# Channel_supply.net
KiCad netlist of a schematic drawn in Altium Designer
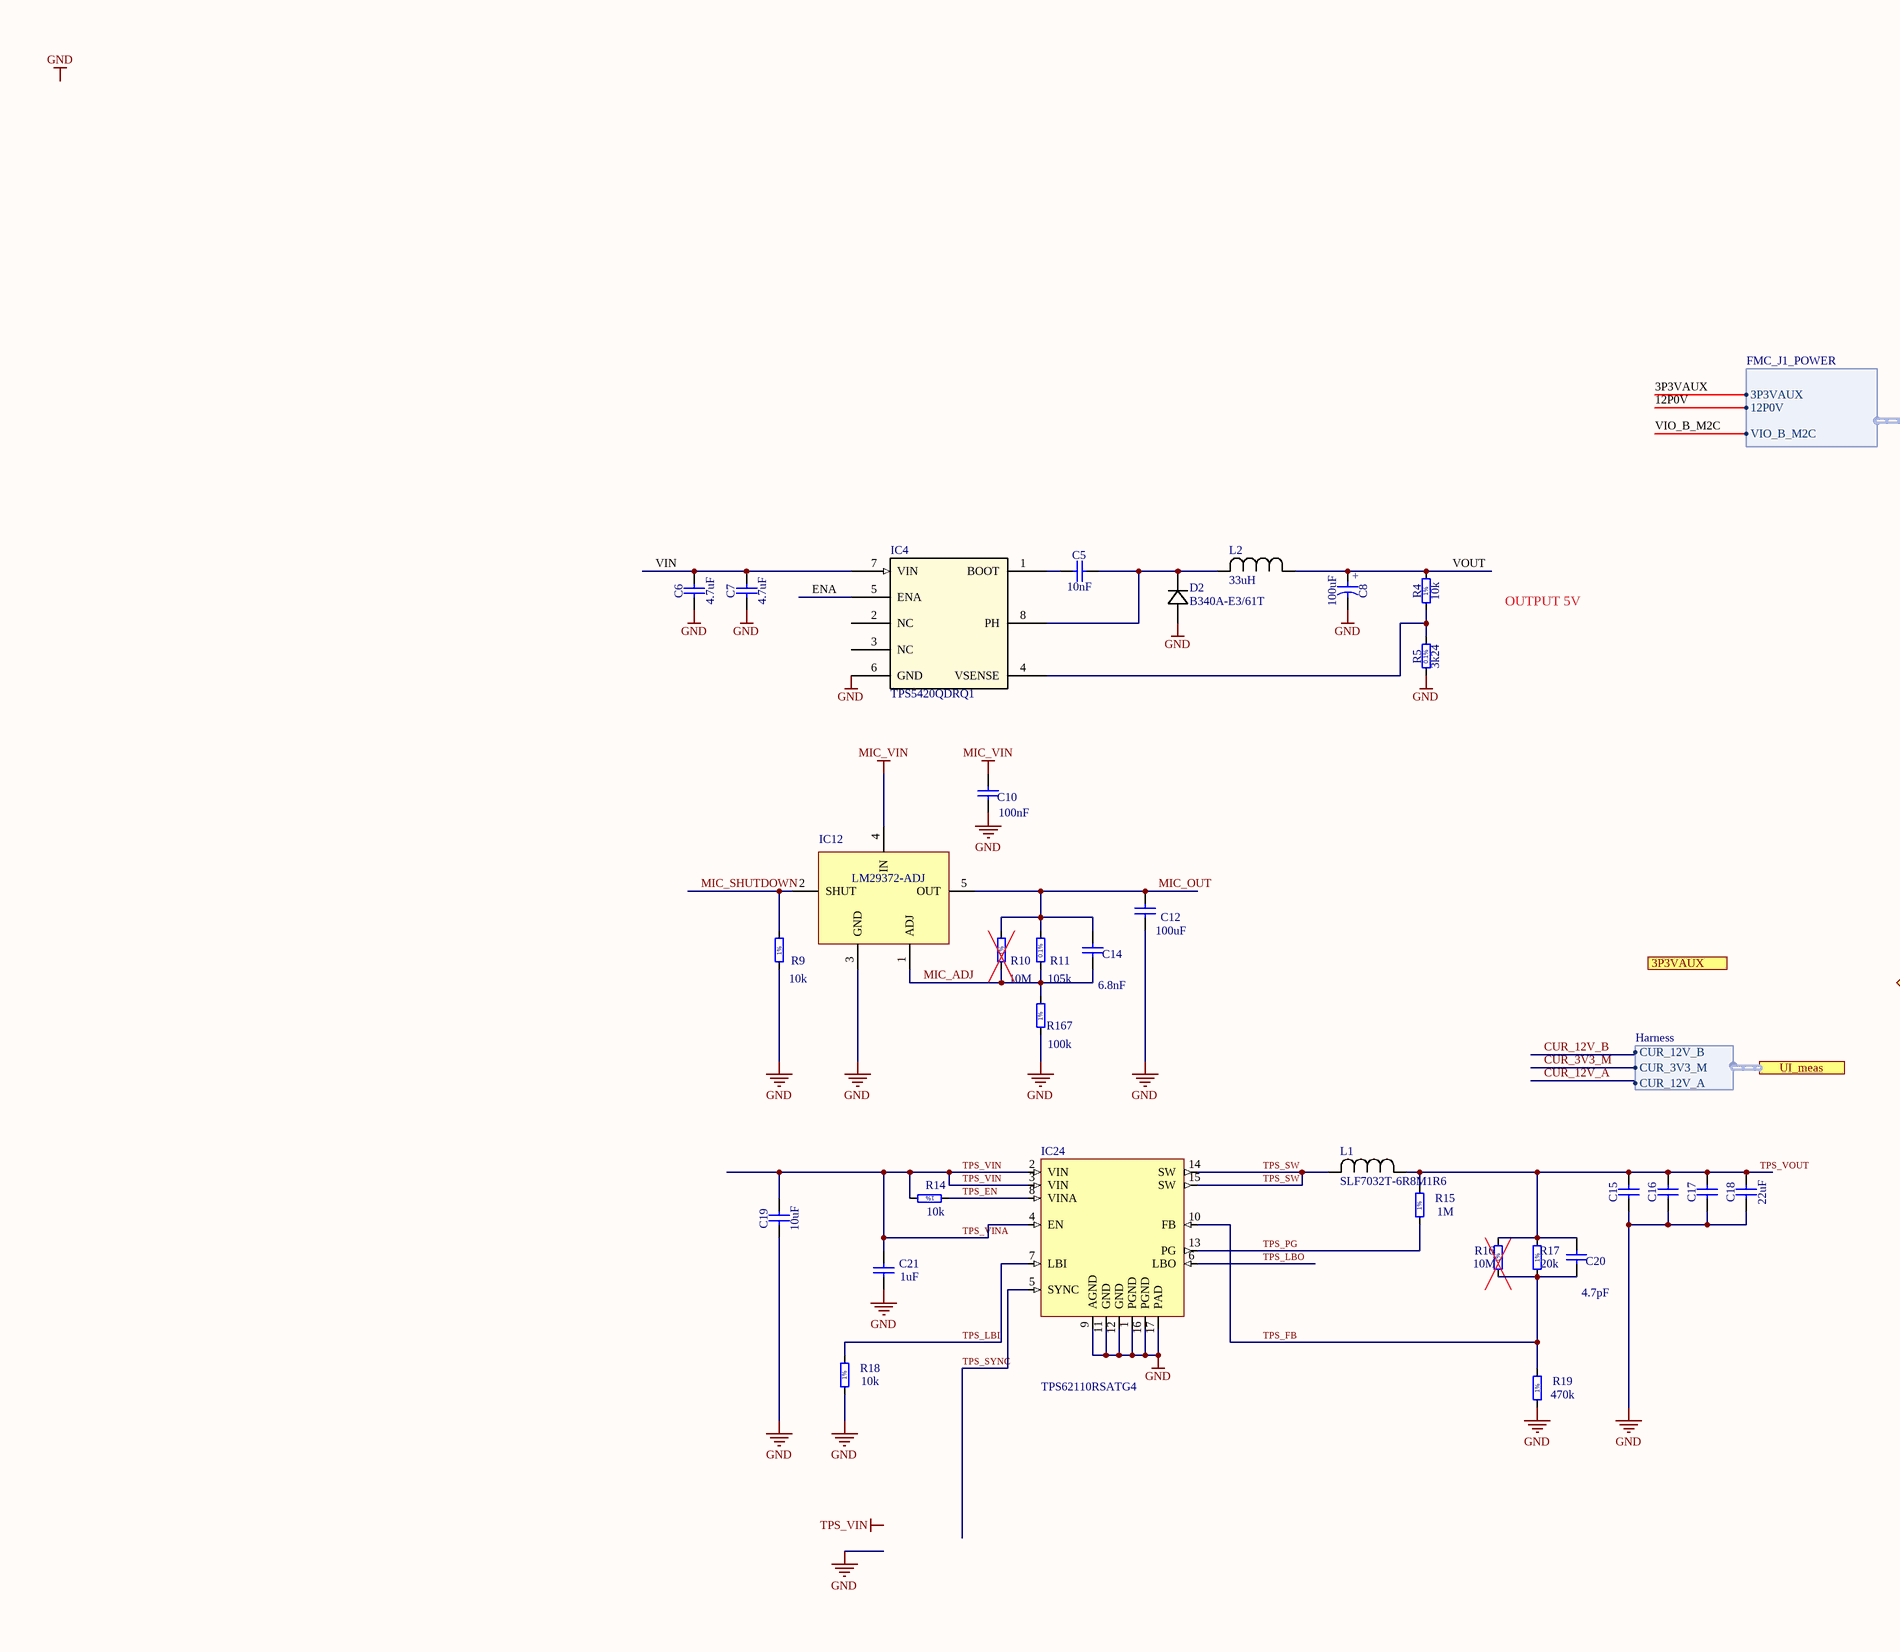
[diagram p0: Channel_supply.SchDoc, left]
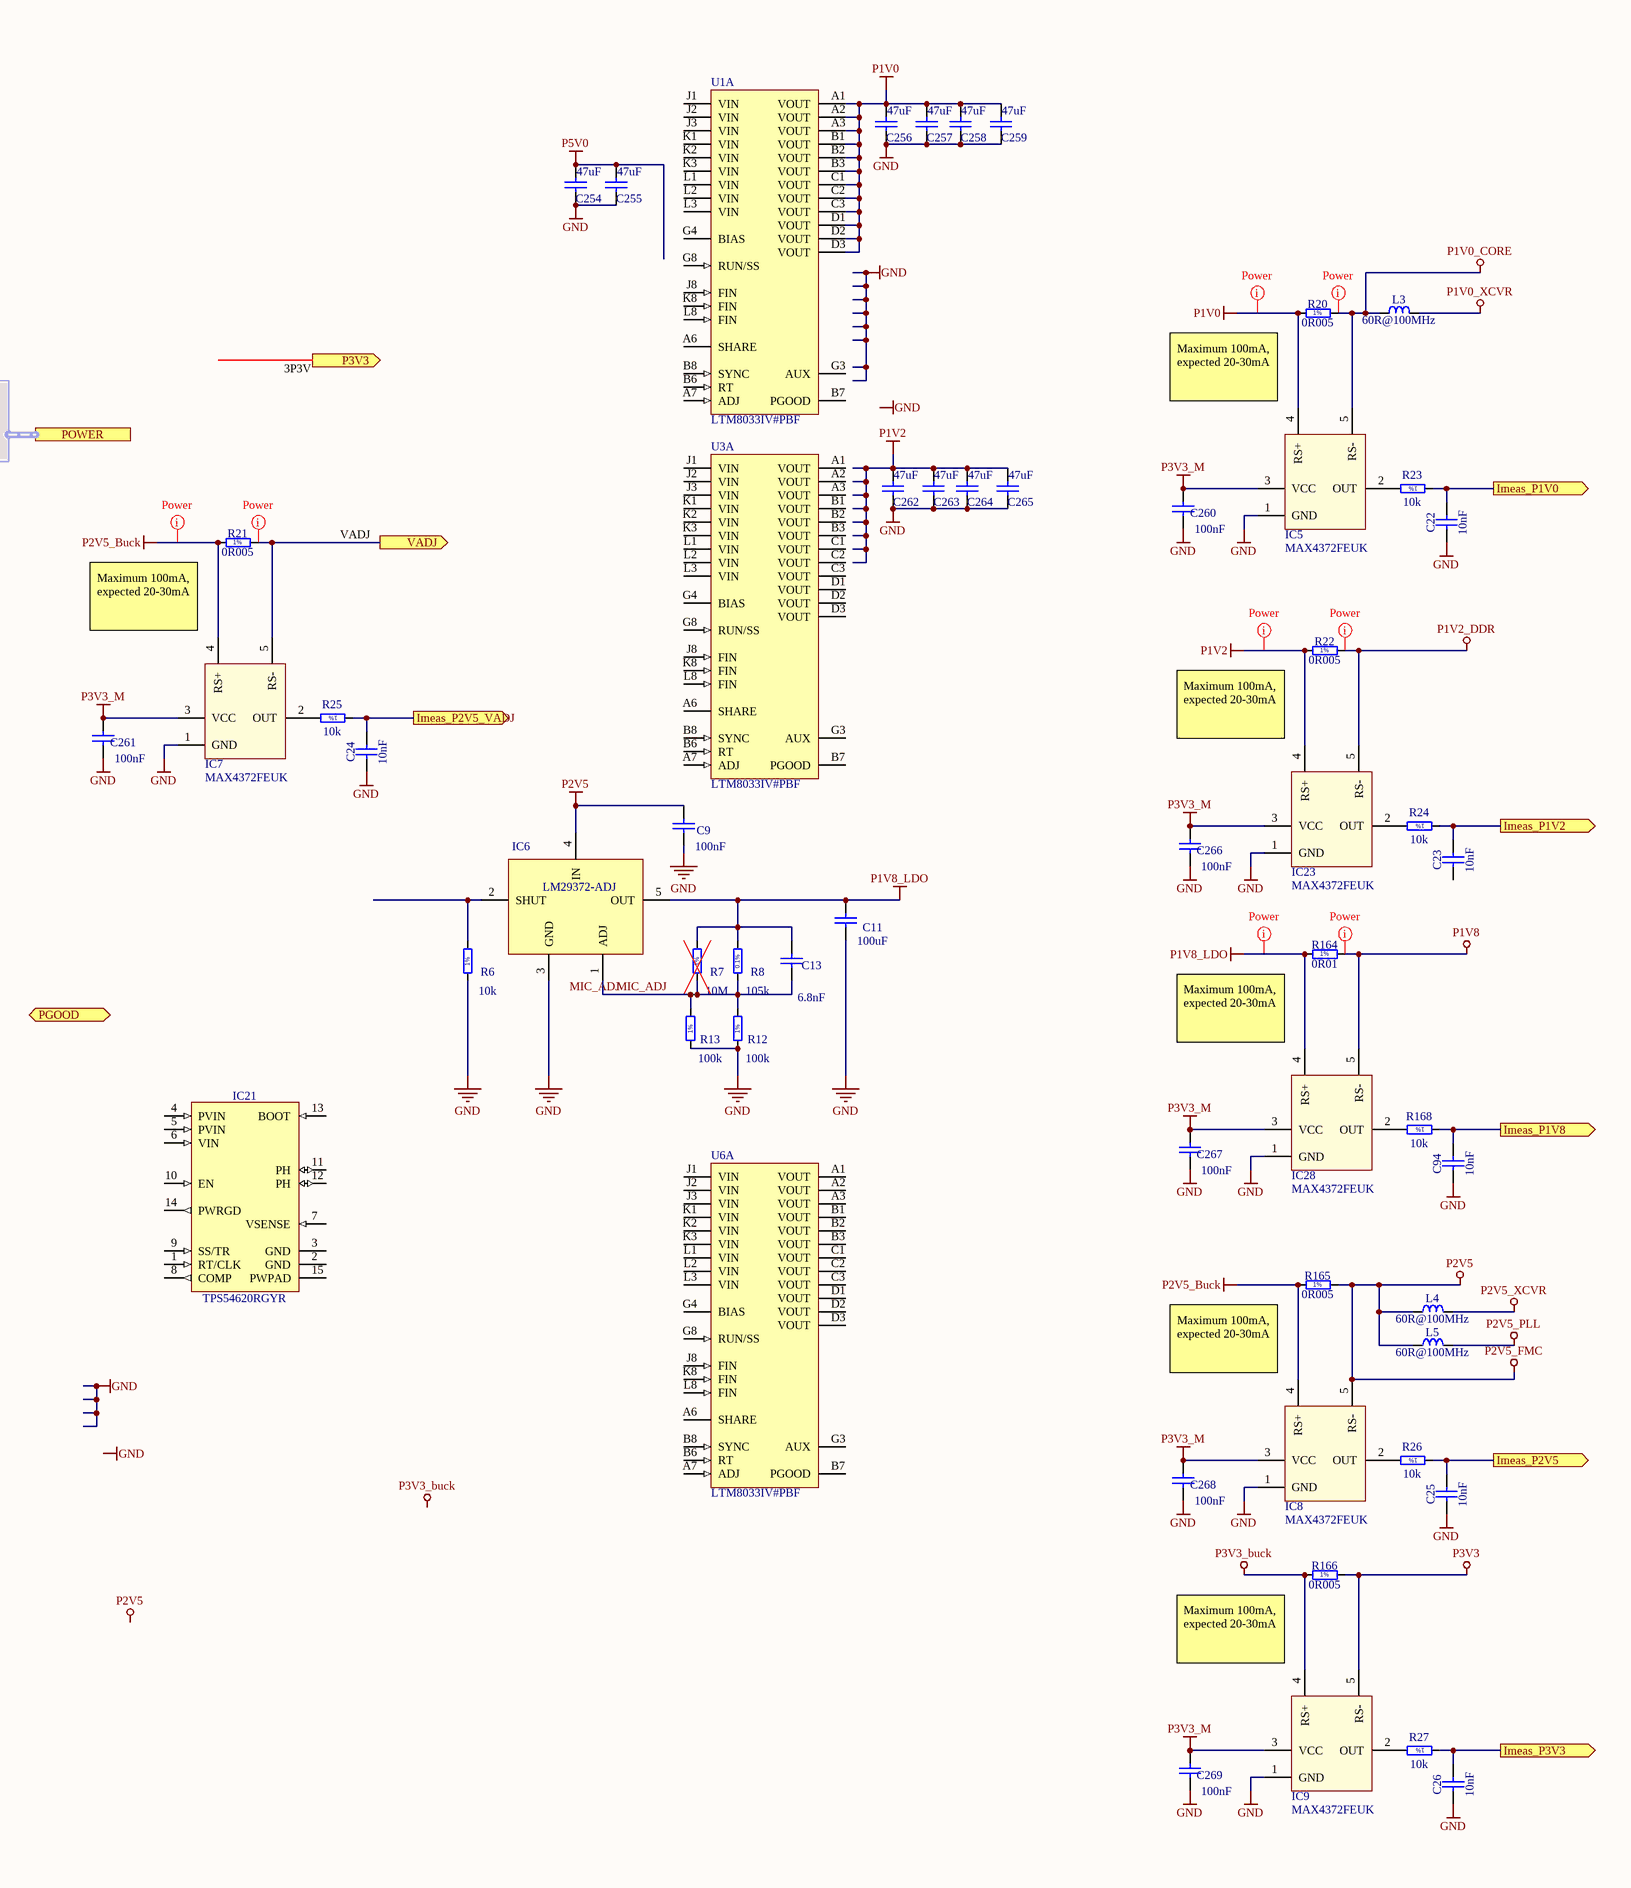
[diagram p1: Channel_supply.SchDoc, right]

(export (version "E")
  (design (tool "Eeschema 10.0.6"))
  (components
    (comp (ref "C5")
      (value "10nF")
      (footprint "CAPC1608X87N")
      (description "Non-polarised capacitor")
      (fields
        (field (name "PART NUMBER") "CC0603_10NF_50V_10%_X7R")
        (field (name "VOLTAGE") "50V")
        (field (name "AUTHOR") "CERN DEM JLC")
      )
      (libsource (lib "Capacitors") (part "Capacitor - non polarized"))
    )
    (comp (ref "C6")
      (value "4.7uF")
      (footprint "CAPC3225X270N")
      (description "Non-polarised capacitor")
      (fields
        (field (name "PART NUMBER") "CC1210_4.7UF_50V_10%_X7R")
        (field (name "VOLTAGE") "50V")
        (field (name "AUTHOR") "CERN DEM JLC")
      )
      (libsource (lib "Capacitors") (part "Capacitor - non polarized"))
    )
    (comp (ref "C7")
      (value "4.7uF")
      (footprint "CAPC3225X270N")
      (description "Non-polarised capacitor")
      (fields
        (field (name "PART NUMBER") "CC1210_4.7UF_50V_10%_X7R")
        (field (name "VOLTAGE") "50V")
        (field (name "AUTHOR") "CERN DEM JLC")
      )
      (libsource (lib "Capacitors") (part "Capacitor - non polarized"))
    )
    (comp (ref "C8")
      (value "100uF")
      (footprint "CAPMP7343X310N")
      (description "Polarised capacitor")
      (fields
        (field (name "PART NUMBER") "100uF 2917 20% ESR=80mOhms AEC-Q200")
        (field (name "VOLTAGE") "10V")
        (field (name "AUTHOR") "CERN DEM JLC")
      )
      (libsource (lib "Capacitors") (part "Capacitor - polarized"))
    )
    (comp (ref "C9")
      (value "100nF")
      (footprint "CAPC1608X87N")
      (description "Non-polarised capacitor")
      (fields
        (field (name "PART NUMBER") "CC0603_100NF_50V_10%_X7R")
        (field (name "VOLTAGE") "50V")
        (field (name "AUTHOR") "CERN DEM JLC")
      )
      (libsource (lib "Capacitors") (part "Capacitor - non polarized"))
    )
    (comp (ref "C10")
      (value "100nF")
      (footprint "CAPC1608X87N")
      (description "Non-polarised capacitor")
      (fields
        (field (name "PART NUMBER") "CC0603_100NF_50V_10%_X7R")
        (field (name "VOLTAGE") "50V")
        (field (name "AUTHOR") "CERN DEM JLC")
      )
      (libsource (lib "Capacitors") (part "Capacitor - non polarized"))
    )
    (comp (ref "C11")
      (value "100uF")
      (footprint "CAPC3216X190N")
      (description "Non-polarised capacitor")
      (fields
        (field (name "PART NUMBER") "CC1206_100UF_10V_20%_X5R")
        (field (name "VOLTAGE") "10V")
        (field (name "AUTHOR") "CERN DEM MR")
      )
      (libsource (lib "Capacitors") (part "Capacitor - non polarized"))
    )
    (comp (ref "C12")
      (value "100uF")
      (footprint "CAPC3216X190N")
      (description "Non-polarised capacitor")
      (fields
        (field (name "PART NUMBER") "CC1206_100UF_10V_20%_X5R")
        (field (name "VOLTAGE") "10V")
        (field (name "AUTHOR") "CERN DEM MR")
      )
      (libsource (lib "Capacitors") (part "Capacitor - non polarized"))
    )
    (comp (ref "C13")
      (value "6.8nF")
      (footprint "CAPC1608X87N")
      (description "Non-polarised capacitor")
      (fields
        (field (name "PART NUMBER") "CC0603_6.8NF_50V_5%_X7R")
        (field (name "VOLTAGE") "50V")
        (field (name "AUTHOR") "CERN DEM JLC")
      )
      (libsource (lib "Capacitors") (part "Capacitor - non polarized"))
    )
    (comp (ref "C14")
      (value "6.8nF")
      (footprint "CAPC1608X87N")
      (description "Non-polarised capacitor")
      (fields
        (field (name "PART NUMBER") "CC0603_6.8NF_50V_5%_X7R")
        (field (name "VOLTAGE") "50V")
        (field (name "AUTHOR") "CERN DEM JLC")
      )
      (libsource (lib "Capacitors") (part "Capacitor - non polarized"))
    )
    (comp (ref "C15")
      (value "22uF")
      (footprint "CAPC3225X270N")
      (description "Non-polarised capacitor")
      (fields
        (field (name "PART NUMBER") "CC1210_22UF_16V_10%_X7R_YUDEN_EMK325B7226KMH")
        (field (name "VOLTAGE") "16V")
        (field (name "AUTHOR") "CERN DEM BC")
      )
      (libsource (lib "Capacitors") (part "Capacitor - non polarized"))
    )
    (comp (ref "C16")
      (value "22uF")
      (footprint "CAPC3225X270N")
      (description "Non-polarised capacitor")
      (fields
        (field (name "PART NUMBER") "CC1210_22UF_16V_10%_X7R_YUDEN_EMK325B7226KMH")
        (field (name "VOLTAGE") "16V")
        (field (name "AUTHOR") "CERN DEM BC")
      )
      (libsource (lib "Capacitors") (part "Capacitor - non polarized"))
    )
    (comp (ref "C17")
      (value "22uF")
      (footprint "CAPC3225X270N")
      (description "Non-polarised capacitor")
      (fields
        (field (name "PART NUMBER") "CC1210_22UF_16V_10%_X7R_YUDEN_EMK325B7226KMH")
        (field (name "VOLTAGE") "16V")
        (field (name "AUTHOR") "CERN DEM BC")
      )
      (libsource (lib "Capacitors") (part "Capacitor - non polarized"))
    )
    (comp (ref "C18")
      (value "22uF")
      (footprint "CAPC3225X270N")
      (description "Non-polarised capacitor")
      (fields
        (field (name "PART NUMBER") "CC1210_22UF_16V_10%_X7R_YUDEN_EMK325B7226KMH")
        (field (name "VOLTAGE") "16V")
        (field (name "AUTHOR") "CERN DEM BC")
      )
      (libsource (lib "Capacitors") (part "Capacitor - non polarized"))
    )
    (comp (ref "C19")
      (value "10uF")
      (footprint "CAPC3225X270N")
      (description "Non-polarised capacitor")
      (fields
        (field (name "PART NUMBER") "CC1210_10UF_25V_10%_X7R")
        (field (name "VOLTAGE") "25V")
        (field (name "AUTHOR") "CERN DEM JLC")
      )
      (libsource (lib "Capacitors") (part "Capacitor - non polarized"))
    )
    (comp (ref "C20")
      (value "4.7pF")
      (footprint "CAPC1608X87N")
      (description "Non-polarised capacitor")
      (fields
        (field (name "PART NUMBER") "CC0603_4.7PF_50V_0.25PF_NP0")
        (field (name "VOLTAGE") "50V")
        (field (name "AUTHOR") "CERN DEM JLC")
      )
      (libsource (lib "Capacitors") (part "Capacitor - non polarized"))
    )
    (comp (ref "C21")
      (value "1uF")
      (footprint "CAPC1608X87N")
      (description "Non-polarised capacitor")
      (fields
        (field (name "PART NUMBER") "CC0603_1UF_25V_10%_X7R")
        (field (name "VOLTAGE") "25V")
        (field (name "AUTHOR") "CERN DEM JLC")
      )
      (libsource (lib "Capacitors") (part "Capacitor - non polarized"))
    )
    (comp (ref "C22")
      (value "10nF")
      (footprint "CAPC1608X87N")
      (description "Non-polarised capacitor")
      (fields
        (field (name "PART NUMBER") "CC0603_10NF_50V_10%_X7R")
        (field (name "VOLTAGE") "50V")
        (field (name "AUTHOR") "CERN DEM JLC")
      )
      (libsource (lib "Capacitors") (part "Capacitor - non polarized"))
    )
    (comp (ref "C23")
      (value "10nF")
      (footprint "CAPC1608X87N")
      (description "Non-polarised capacitor")
      (fields
        (field (name "PART NUMBER") "CC0603_10NF_50V_10%_X7R")
        (field (name "VOLTAGE") "50V")
        (field (name "AUTHOR") "CERN DEM JLC")
      )
      (libsource (lib "Capacitors") (part "Capacitor - non polarized"))
    )
    (comp (ref "C24")
      (value "10nF")
      (footprint "CAPC1608X87N")
      (description "Non-polarised capacitor")
      (fields
        (field (name "PART NUMBER") "CC0603_10NF_50V_10%_X7R")
        (field (name "VOLTAGE") "50V")
        (field (name "AUTHOR") "CERN DEM JLC")
      )
      (libsource (lib "Capacitors") (part "Capacitor - non polarized"))
    )
    (comp (ref "C25")
      (value "10nF")
      (footprint "CAPC1608X87N")
      (description "Non-polarised capacitor")
      (fields
        (field (name "PART NUMBER") "CC0603_10NF_50V_10%_X7R")
        (field (name "VOLTAGE") "50V")
        (field (name "AUTHOR") "CERN DEM JLC")
      )
      (libsource (lib "Capacitors") (part "Capacitor - non polarized"))
    )
    (comp (ref "C26")
      (value "10nF")
      (footprint "CAPC1608X87N")
      (description "Non-polarised capacitor")
      (fields
        (field (name "PART NUMBER") "CC0603_10NF_50V_10%_X7R")
        (field (name "VOLTAGE") "50V")
        (field (name "AUTHOR") "CERN DEM JLC")
      )
      (libsource (lib "Capacitors") (part "Capacitor - non polarized"))
    )
    (comp (ref "C94")
      (value "10nF")
      (footprint "CAPC1608X87N")
      (description "Non-polarised capacitor")
      (fields
        (field (name "PART NUMBER") "CC0603_10NF_50V_10%_X7R")
        (field (name "VOLTAGE") "50V")
        (field (name "AUTHOR") "CERN DEM JLC")
      )
      (libsource (lib "Capacitors") (part "Capacitor - non polarized"))
    )
    (comp (ref "C254")
      (value "47uF")
      (footprint "CAPC2012X140N")
      (description "Non-polarised capacitor")
      (fields
        (field (name "PART NUMBER") "CC0805_47UF_6.3V_20%_X5R")
        (field (name "MANUFACTURER") "GENERIC")
        (field (name "AUTHOR") "CERN DEM JLC")
      )
      (libsource (lib "Capacitors") (part "Capacitor - non polarized"))
    )
    (comp (ref "C255")
      (value "47uF")
      (footprint "CAPC2012X140N")
      (description "Non-polarised capacitor")
      (fields
        (field (name "PART NUMBER") "CC0805_47UF_6.3V_20%_X5R")
        (field (name "MANUFACTURER") "GENERIC")
        (field (name "AUTHOR") "CERN DEM JLC")
      )
      (libsource (lib "Capacitors") (part "Capacitor - non polarized"))
    )
    (comp (ref "C256")
      (value "47uF")
      (footprint "CAPC2012X140N")
      (description "Non-polarised capacitor")
      (fields
        (field (name "PART NUMBER") "CC0805_47UF_6.3V_20%_X5R")
        (field (name "MANUFACTURER") "GENERIC")
        (field (name "AUTHOR") "CERN DEM JLC")
      )
      (libsource (lib "Capacitors") (part "Capacitor - non polarized"))
    )
    (comp (ref "C257")
      (value "47uF")
      (footprint "CAPC2012X140N")
      (description "Non-polarised capacitor")
      (fields
        (field (name "PART NUMBER") "CC0805_47UF_6.3V_20%_X5R")
        (field (name "MANUFACTURER") "GENERIC")
        (field (name "AUTHOR") "CERN DEM JLC")
      )
      (libsource (lib "Capacitors") (part "Capacitor - non polarized"))
    )
    (comp (ref "C258")
      (value "47uF")
      (footprint "CAPC2012X140N")
      (description "Non-polarised capacitor")
      (fields
        (field (name "PART NUMBER") "CC0805_47UF_6.3V_20%_X5R")
        (field (name "MANUFACTURER") "GENERIC")
        (field (name "AUTHOR") "CERN DEM JLC")
      )
      (libsource (lib "Capacitors") (part "Capacitor - non polarized"))
    )
    (comp (ref "C259")
      (value "47uF")
      (footprint "CAPC2012X140N")
      (description "Non-polarised capacitor")
      (fields
        (field (name "PART NUMBER") "CC0805_47UF_6.3V_20%_X5R")
        (field (name "MANUFACTURER") "GENERIC")
        (field (name "AUTHOR") "CERN DEM JLC")
      )
      (libsource (lib "Capacitors") (part "Capacitor - non polarized"))
    )
    (comp (ref "C260")
      (value "100nF")
      (footprint "CAPC1608X87N")
      (description "Non-polarised capacitor")
      (fields
        (field (name "PART NUMBER") "CC0603_100NF_50V_10%_X7R")
        (field (name "VOLTAGE") "50V")
        (field (name "AUTHOR") "CERN DEM JLC")
      )
      (libsource (lib "Capacitors") (part "Capacitor - non polarized"))
    )
    (comp (ref "C261")
      (value "100nF")
      (footprint "CAPC1608X87N")
      (description "Non-polarised capacitor")
      (fields
        (field (name "PART NUMBER") "CC0603_100NF_50V_10%_X7R")
        (field (name "VOLTAGE") "50V")
        (field (name "AUTHOR") "CERN DEM JLC")
      )
      (libsource (lib "Capacitors") (part "Capacitor - non polarized"))
    )
    (comp (ref "C262")
      (value "47uF")
      (footprint "CAPC2012X140N")
      (description "Non-polarised capacitor")
      (fields
        (field (name "PART NUMBER") "CC0805_47UF_6.3V_20%_X5R")
        (field (name "MANUFACTURER") "GENERIC")
        (field (name "AUTHOR") "CERN DEM JLC")
      )
      (libsource (lib "Capacitors") (part "Capacitor - non polarized"))
    )
    (comp (ref "C263")
      (value "47uF")
      (footprint "CAPC2012X140N")
      (description "Non-polarised capacitor")
      (fields
        (field (name "PART NUMBER") "CC0805_47UF_6.3V_20%_X5R")
        (field (name "MANUFACTURER") "GENERIC")
        (field (name "AUTHOR") "CERN DEM JLC")
      )
      (libsource (lib "Capacitors") (part "Capacitor - non polarized"))
    )
    (comp (ref "C264")
      (value "47uF")
      (footprint "CAPC2012X140N")
      (description "Non-polarised capacitor")
      (fields
        (field (name "PART NUMBER") "CC0805_47UF_6.3V_20%_X5R")
        (field (name "MANUFACTURER") "GENERIC")
        (field (name "AUTHOR") "CERN DEM JLC")
      )
      (libsource (lib "Capacitors") (part "Capacitor - non polarized"))
    )
    (comp (ref "C265")
      (value "47uF")
      (footprint "CAPC2012X140N")
      (description "Non-polarised capacitor")
      (fields
        (field (name "PART NUMBER") "CC0805_47UF_6.3V_20%_X5R")
        (field (name "MANUFACTURER") "GENERIC")
        (field (name "AUTHOR") "CERN DEM JLC")
      )
      (libsource (lib "Capacitors") (part "Capacitor - non polarized"))
    )
    (comp (ref "C266")
      (value "100nF")
      (footprint "CAPC1608X87N")
      (description "Non-polarised capacitor")
      (fields
        (field (name "PART NUMBER") "CC0603_100NF_50V_10%_X7R")
        (field (name "VOLTAGE") "50V")
        (field (name "AUTHOR") "CERN DEM JLC")
      )
      (libsource (lib "Capacitors") (part "Capacitor - non polarized"))
    )
    (comp (ref "C267")
      (value "100nF")
      (footprint "CAPC1608X87N")
      (description "Non-polarised capacitor")
      (fields
        (field (name "PART NUMBER") "CC0603_100NF_50V_10%_X7R")
        (field (name "VOLTAGE") "50V")
        (field (name "AUTHOR") "CERN DEM JLC")
      )
      (libsource (lib "Capacitors") (part "Capacitor - non polarized"))
    )
    (comp (ref "C268")
      (value "100nF")
      (footprint "CAPC1608X87N")
      (description "Non-polarised capacitor")
      (fields
        (field (name "PART NUMBER") "CC0603_100NF_50V_10%_X7R")
        (field (name "VOLTAGE") "50V")
        (field (name "AUTHOR") "CERN DEM JLC")
      )
      (libsource (lib "Capacitors") (part "Capacitor - non polarized"))
    )
    (comp (ref "C269")
      (value "100nF")
      (footprint "CAPC1608X87N")
      (description "Non-polarised capacitor")
      (fields
        (field (name "PART NUMBER") "CC0603_100NF_50V_10%_X7R")
        (field (name "VOLTAGE") "50V")
        (field (name "AUTHOR") "CERN DEM JLC")
      )
      (libsource (lib "Capacitors") (part "Capacitor - non polarized"))
    )
    (comp (ref "D2")
      (value "B340A-E3/61T")
      (footprint "DO-214AC")
      (description "Diode Schottky 3A/40V")
      (fields (field (name "MANUFACTURER") "Vishay"))
      (libsource (lib "LIBRARY_SCH") (part "D_B340A-E3/61T"))
    )
    (comp (ref "IC4")
      (value "TPS5420QDRQ1")
      (footprint "SOIC D8")
      (description "Buck converter")
      (fields (field (name "MANUFACTURER") "TI"))
      (libsource (lib "LIBRARY_SCH") (part "PM_TPS5420QDRQ1"))
    )
    (comp (ref "IC5")
      (value "MAX4372FEUK")
      (footprint "SOT95P270X145-5N")
      (fields (field (name "MANUFACTURER") "Maxim"))
      (libsource (lib "LIBRARY_SCH") (part "PM_MAX4372FEUK"))
    )
    (comp (ref "IC6")
      (value "LM29372-ADJ")
      (footprint "DPAK170P1524X460-6N")
      (description "LDO 750mA ADJ")
      (fields
        (field (name "PART NUMBER") "LM29372")
        (field (name "MANUFACTURER") "MICREL - MICROCHIP")
        (field (name "AUTHOR") "DKaczmara")
      )
      (libsource (lib "LIBRARY_SCH") (part "REG_MIC29372"))
    )
    (comp (ref "IC7")
      (value "MAX4372FEUK")
      (footprint "SOT95P270X145-5N")
      (fields (field (name "MANUFACTURER") "Maxim"))
      (libsource (lib "LIBRARY_SCH") (part "PM_MAX4372FEUK"))
    )
    (comp (ref "IC8")
      (value "MAX4372FEUK")
      (footprint "SOT95P270X145-5N")
      (fields (field (name "MANUFACTURER") "Maxim"))
      (libsource (lib "LIBRARY_SCH") (part "PM_MAX4372FEUK"))
    )
    (comp (ref "IC9")
      (value "MAX4372FEUK")
      (footprint "SOT95P270X145-5N")
      (fields (field (name "MANUFACTURER") "Maxim"))
      (libsource (lib "LIBRARY_SCH") (part "PM_MAX4372FEUK"))
    )
    (comp (ref "IC12")
      (value "LM29372-ADJ")
      (footprint "DPAK170P1524X460-6N")
      (description "LDO 750mA ADJ")
      (fields
        (field (name "PART NUMBER") "LM29372")
        (field (name "MANUFACTURER") "MICREL - MICROCHIP")
        (field (name "AUTHOR") "DKaczmara")
      )
      (libsource (lib "DK-lib") (part "REG_MIC29372"))
    )
    (comp (ref "IC21")
      (value "TPS54620RGYR")
      (footprint "TEXAS_RGY (S-PVQFN-N14)")
      (description "17V Input, 6A Output, Synchronous Step Down Switcher")
      (fields (field (name "MANUFACTURER") "TEXAS INSTRUMENTS") (field (name "AUTHOR") "CERN DEM JLC"))
      (libsource (lib "ICs And Semiconductors") (part "TPS54620"))
    )
    (comp (ref "IC23")
      (value "MAX4372FEUK")
      (footprint "SOT95P270X145-5N")
      (fields (field (name "MANUFACTURER") "Maxim"))
      (libsource (lib "LIBRARY_SCH") (part "PM_MAX4372FEUK"))
    )
    (comp (ref "IC24")
      (value "TPS62110RSATG4")
      (footprint "QFN127P600-16")
      (libsource (lib "LIBRARY_SCH") (part "PM_TPS62110"))
    )
    (comp (ref "IC28")
      (value "MAX4372FEUK")
      (footprint "SOT95P270X145-5N")
      (fields (field (name "MANUFACTURER") "Maxim"))
      (libsource (lib "LIBRARY_SCH") (part "PM_MAX4372FEUK"))
    )
    (comp (ref "L1")
      (value "SLF7032T-6R8M1R6")
      (footprint "IND_7030")
      (description "Imported")
      (fields (field (name "MANUFACTURER_PART_NUMBER") "SLF7032T-6R8M1R6-2"))
      (libsource (lib "LIBRARY_SCH") (part "L_SLF7032T-6R8M1R6"))
    )
    (comp (ref "L2")
      (value "33uH")
      (footprint "IND_12x12")
      (fields
        (field (name "MANUFACTURER") "Coilcraft")
        (field (name "MANUFACTURER PART NUMBER") "MSS1260-333MLD")
      )
      (libsource (lib "LIBRARY_SCH") (part "L_POW_MSS1260-333MLD"))
    )
    (comp (ref "L3")
      (value "60R@100MHz")
      (footprint "INDC4516X180N")
      (description "Inductor")
      (fields
        (field (name "PART NUMBER") "IND1806_MURATA_BLM41PG600SN1L")
        (field (name "POWER") "6A")
        (field (name "AUTHOR") "CERN DEM JLC")
      )
      (libsource (lib "Inductors & Transformers") (part "Inductor"))
    )
    (comp (ref "L4")
      (value "60R@100MHz")
      (footprint "INDC4516X180N")
      (description "Inductor")
      (fields
        (field (name "PART NUMBER") "IND1806_MURATA_BLM41PG600SN1L")
        (field (name "POWER") "6A")
        (field (name "AUTHOR") "CERN DEM JLC")
      )
      (libsource (lib "Inductors & Transformers") (part "Inductor"))
    )
    (comp (ref "L5")
      (value "60R@100MHz")
      (footprint "INDC4516X180N")
      (description "Inductor")
      (fields
        (field (name "PART NUMBER") "IND1806_MURATA_BLM41PG600SN1L")
        (field (name "POWER") "6A")
        (field (name "AUTHOR") "CERN DEM JLC")
      )
      (libsource (lib "Inductors & Transformers") (part "Inductor"))
    )
    (comp (ref "R4")
      (value "10k")
      (footprint "RESC1608X55N")
      (description "Resistor - 1%")
      (fields
        (field (name "PART NUMBER") "R0603_10K_1%_0.1W_100PPM")
        (field (name "POWER") "0.1W")
        (field (name "AUTHOR") "CERN DEM JLC")
      )
      (libsource (lib "Resistors") (part "Resistor - 1%"))
    )
    (comp (ref "R5")
      (value "3k24")
      (footprint "RESC1608X55N")
      (description "Resistor - 0.1%")
      (fields
        (field (name "PART NUMBER") "R0603_3K24_0.1%_0.063W_10PPM")
        (field (name "POWER") "0.063W")
        (field (name "AUTHOR") "CERN DEM JLC")
      )
      (libsource (lib "Resistors") (part "Resistor - 0.1%"))
    )
    (comp (ref "R6")
      (value "10k")
      (footprint "RESC1608X55N")
      (description "Resistor - 1%")
      (fields
        (field (name "PART NUMBER") "R0603_10K_1%_0.1W_100PPM")
        (field (name "POWER") "0.1W")
        (field (name "AUTHOR") "CERN DEM JLC")
      )
      (libsource (lib "Resistors") (part "Resistor - 1%"))
    )
    (comp (ref "R7")
      (value "10M")
      (footprint "RESC1608X55N")
      (description "Resistor - 1%")
      (fields
        (field (name "PART NUMBER") "R0603_10M_1%_0.1W_100PPM")
        (field (name "POWER") "0.1W")
        (field (name "AUTHOR") "CERN DEM JLC")
      )
      (libsource (lib "Resistors") (part "Resistor - 1%"))
    )
    (comp (ref "R8")
      (value "105k")
      (footprint "RESC1608X55N")
      (description "Resistor - 0.1%")
      (fields
        (field (name "PART NUMBER") "R0603_105K_0.1%_0.063W_10PPM")
        (field (name "POWER") "0.063W")
        (field (name "AUTHOR") "CERN DEM JLC")
      )
      (libsource (lib "Resistors") (part "Resistor - 0.1%"))
    )
    (comp (ref "R9")
      (value "10k")
      (footprint "RESC1608X55N")
      (description "Resistor - 1%")
      (fields
        (field (name "PART NUMBER") "R0603_10K_1%_0.1W_100PPM")
        (field (name "POWER") "0.1W")
        (field (name "AUTHOR") "CERN DEM JLC")
      )
      (libsource (lib "Resistors") (part "Resistor - 1%"))
    )
    (comp (ref "R10")
      (value "10M")
      (footprint "RESC1608X55N")
      (description "Resistor - 1%")
      (fields
        (field (name "PART NUMBER") "R0603_10M_1%_0.1W_100PPM")
        (field (name "POWER") "0.1W")
        (field (name "AUTHOR") "CERN DEM JLC")
      )
      (libsource (lib "Resistors") (part "Resistor - 1%"))
    )
    (comp (ref "R11")
      (value "105k")
      (footprint "RESC1608X55N")
      (description "Resistor - 0.1%")
      (fields
        (field (name "PART NUMBER") "R0603_105K_0.1%_0.063W_10PPM")
        (field (name "POWER") "0.063W")
        (field (name "AUTHOR") "CERN DEM JLC")
      )
      (libsource (lib "Resistors") (part "Resistor - 0.1%"))
    )
    (comp (ref "R12")
      (value "100k")
      (footprint "RESC1608X55N")
      (description "Resistor - 1%")
      (fields
        (field (name "PART NUMBER") "R0603_100K_1%_0.1W_100PPM")
        (field (name "POWER") "0.1W")
        (field (name "AUTHOR") "CERN DEM JLC")
      )
      (libsource (lib "Resistors") (part "Resistor - 1%"))
    )
    (comp (ref "R13")
      (value "100k")
      (footprint "RESC1608X55N")
      (description "Resistor - 1%")
      (fields
        (field (name "PART NUMBER") "R0603_100K_1%_0.1W_100PPM")
        (field (name "POWER") "0.1W")
        (field (name "AUTHOR") "CERN DEM JLC")
      )
      (libsource (lib "Resistors") (part "Resistor - 1%"))
    )
    (comp (ref "R14")
      (value "10k")
      (footprint "RESC1608X55N")
      (description "Resistor - 1%")
      (fields
        (field (name "PART NUMBER") "R0603_10K_1%_0.1W_100PPM")
        (field (name "POWER") "0.1W")
        (field (name "AUTHOR") "CERN DEM JLC")
      )
      (libsource (lib "Resistors") (part "Resistor - 1%"))
    )
    (comp (ref "R15")
      (value "1M")
      (footprint "RESC1608X55N")
      (description "Resistor - 1%")
      (fields
        (field (name "PART NUMBER") "R0603_1M_1%_0.1W_100PPM")
        (field (name "POWER") "0.1W")
        (field (name "AUTHOR") "CERN DEM JLC")
      )
      (libsource (lib "Resistors") (part "Resistor - 1%"))
    )
    (comp (ref "R16")
      (value "10M")
      (footprint "RESC1608X55N")
      (description "Resistor - 1%")
      (fields
        (field (name "PART NUMBER") "R0603_10M_1%_0.1W_100PPM")
        (field (name "POWER") "0.1W")
        (field (name "AUTHOR") "CERN DEM JLC")
      )
      (libsource (lib "Resistors") (part "Resistor - 1%"))
    )
    (comp (ref "R17")
      (value "20k")
      (footprint "RESC1608X55N")
      (description "Resistor - 1%")
      (fields
        (field (name "PART NUMBER") "R0603_20K_1%_0.1W_100PPM")
        (field (name "POWER") "0.1W")
        (field (name "AUTHOR") "CERN DEM JLC")
      )
      (libsource (lib "Resistors") (part "Resistor - 1%"))
    )
    (comp (ref "R18")
      (value "10k")
      (footprint "RESC1608X55N")
      (description "Resistor - 1%")
      (fields
        (field (name "PART NUMBER") "R0603_10K_1%_0.1W_100PPM")
        (field (name "POWER") "0.1W")
        (field (name "AUTHOR") "CERN DEM JLC")
      )
      (libsource (lib "Resistors") (part "Resistor - 1%"))
    )
    (comp (ref "R19")
      (value "470k")
      (footprint "RESC1608X55N")
      (description "Resistor - 1%")
      (fields
        (field (name "PART NUMBER") "R0603_470K_1%_0.1W_100PPM")
        (field (name "POWER") "0.1W")
        (field (name "AUTHOR") "CERN DEM JLC")
      )
      (libsource (lib "Resistors") (part "Resistor - 1%"))
    )
    (comp (ref "R20")
      (value "0R005")
      (footprint "RESC3216X80N")
      (description "Resistor - 1%")
      (fields
        (field (name "PART NUMBER") "R1206_0R005_1%_1W_100PPM_TT_LRMAM1206")
        (field (name "POWER") "1W")
        (field (name "AUTHOR") "CERN DEM BC")
      )
      (libsource (lib "Resistors") (part "Resistor - 1%"))
    )
    (comp (ref "R21")
      (value "0R005")
      (footprint "RESC3216X80N")
      (description "Resistor - 1%")
      (fields
        (field (name "PART NUMBER") "R1206_0R005_1%_1W_100PPM_TT_LRMAM1206")
        (field (name "POWER") "1W")
        (field (name "AUTHOR") "CERN DEM BC")
      )
      (libsource (lib "Resistors") (part "Resistor - 1%"))
    )
    (comp (ref "R22")
      (value "0R005")
      (footprint "RESC3216X80N")
      (description "Resistor - 1%")
      (fields
        (field (name "PART NUMBER") "R1206_0R005_1%_1W_100PPM_TT_LRMAM1206")
        (field (name "POWER") "1W")
        (field (name "AUTHOR") "CERN DEM BC")
      )
      (libsource (lib "Resistors") (part "Resistor - 1%"))
    )
    (comp (ref "R23")
      (value "10k")
      (footprint "RESC1608X55N")
      (description "Resistor - 1%")
      (fields
        (field (name "PART NUMBER") "R0603_10K_1%_0.1W_100PPM")
        (field (name "POWER") "0.1W")
        (field (name "AUTHOR") "CERN DEM JLC")
      )
      (libsource (lib "Resistors") (part "Resistor - 1%"))
    )
    (comp (ref "R24")
      (value "10k")
      (footprint "RESC1608X55N")
      (description "Resistor - 1%")
      (fields
        (field (name "PART NUMBER") "R0603_10K_1%_0.1W_100PPM")
        (field (name "POWER") "0.1W")
        (field (name "AUTHOR") "CERN DEM JLC")
      )
      (libsource (lib "Resistors") (part "Resistor - 1%"))
    )
    (comp (ref "R25")
      (value "10k")
      (footprint "RESC1608X55N")
      (description "Resistor - 1%")
      (fields
        (field (name "PART NUMBER") "R0603_10K_1%_0.1W_100PPM")
        (field (name "POWER") "0.1W")
        (field (name "AUTHOR") "CERN DEM JLC")
      )
      (libsource (lib "Resistors") (part "Resistor - 1%"))
    )
    (comp (ref "R26")
      (value "10k")
      (footprint "RESC1608X55N")
      (description "Resistor - 1%")
      (fields
        (field (name "PART NUMBER") "R0603_10K_1%_0.1W_100PPM")
        (field (name "POWER") "0.1W")
        (field (name "AUTHOR") "CERN DEM JLC")
      )
      (libsource (lib "Resistors") (part "Resistor - 1%"))
    )
    (comp (ref "R27")
      (value "10k")
      (footprint "RESC1608X55N")
      (description "Resistor - 1%")
      (fields
        (field (name "PART NUMBER") "R0603_10K_1%_0.1W_100PPM")
        (field (name "POWER") "0.1W")
        (field (name "AUTHOR") "CERN DEM JLC")
      )
      (libsource (lib "Resistors") (part "Resistor - 1%"))
    )
    (comp (ref "R164")
      (value "0R01")
      (footprint "RESC3216X80N")
      (description "Resistor - 1%")
      (fields
        (field (name "PART NUMBER") "R1206_0R01_1%_1W_100PPM_TT_LRMAM1206")
        (field (name "POWER") "1W")
        (field (name "AUTHOR") "CERN DEM BC")
      )
      (libsource (lib "Resistors") (part "Resistor - 1%"))
    )
    (comp (ref "R165")
      (value "0R005")
      (footprint "RESC3216X80N")
      (description "Resistor - 1%")
      (fields
        (field (name "PART NUMBER") "R1206_0R005_1%_1W_100PPM_TT_LRMAM1206")
        (field (name "POWER") "1W")
        (field (name "AUTHOR") "CERN DEM BC")
      )
      (libsource (lib "Resistors") (part "Resistor - 1%"))
    )
    (comp (ref "R166")
      (value "0R005")
      (footprint "RESC3216X80N")
      (description "Resistor - 1%")
      (fields
        (field (name "PART NUMBER") "R1206_0R005_1%_1W_100PPM_TT_LRMAM1206")
        (field (name "POWER") "1W")
        (field (name "AUTHOR") "CERN DEM BC")
      )
      (libsource (lib "Resistors") (part "Resistor - 1%"))
    )
    (comp (ref "R167")
      (value "100k")
      (footprint "RESC1608X55N")
      (description "Resistor - 1%")
      (fields
        (field (name "PART NUMBER") "R0603_100K_1%_0.1W_100PPM")
        (field (name "POWER") "0.1W")
        (field (name "AUTHOR") "CERN DEM JLC")
      )
      (libsource (lib "Resistors") (part "Resistor - 1%"))
    )
    (comp (ref "R168")
      (value "10k")
      (footprint "RESC1608X55N")
      (description "Resistor - 1%")
      (fields
        (field (name "PART NUMBER") "R0603_10K_1%_0.1W_100PPM")
        (field (name "POWER") "0.1W")
        (field (name "AUTHOR") "CERN DEM JLC")
      )
      (libsource (lib "Resistors") (part "Resistor - 1%"))
    )
    (comp (ref "U1")
      (value "LTM8033IV#PBF")
      (footprint "LT-LGA-76-15000X11250X4320_V")
      (description "Ultralow Noise EMC 36 VIN, 3 A DC/DC uModule Regulator, 76-pin LGA, -40 to 125 degC, Pb-Free, Tray")
      (fields (field (name "MANUFACTURER") "Linear Technology"))
      (libsource (lib "Altium Content Vault") (part "LT-LTM8033-LGA-76"))
    )
    (comp (ref "U3")
      (value "LTM8033IV#PBF")
      (footprint "LT-LGA-76-15000X11250X4320_V")
      (description "Ultralow Noise EMC 36 VIN, 3 A DC/DC uModule Regulator, 76-pin LGA, -40 to 125 degC, Pb-Free, Tray")
      (fields (field (name "MANUFACTURER") "Linear Technology"))
      (libsource (lib "Altium Content Vault") (part "LT-LTM8033-LGA-76"))
    )
    (comp (ref "U6")
      (value "LTM8033IV#PBF")
      (footprint "LT-LGA-76-15000X11250X4320_V")
      (description "Ultralow Noise EMC 36 VIN, 3 A DC/DC uModule Regulator, 76-pin LGA, -40 to 125 degC, Pb-Free, Tray")
      (fields (field (name "MANUFACTURER") "Linear Technology"))
      (libsource (lib "Altium Content Vault") (part "LT-LTM8033-LGA-76"))
    )
  )
  (nets
    (net (code "8") (name "/ENA") (class "Default")
      (node (ref "IC4") (pin "5") (pinfunction "ENA_5") (pintype "passive"))
    )
    (net (code "9") (name "/Imeas_P1V0") (class "Default")
      (node (ref "C22") (pin "2") (pinfunction "2_2") (pintype "passive"))
      (node (ref "R23") (pin "1") (pinfunction "1_1") (pintype "passive"))
    )
    (net (code "10") (name "/Imeas_P1V2") (class "Default")
      (node (ref "C23") (pin "2") (pinfunction "2_2") (pintype "passive"))
      (node (ref "R24") (pin "1") (pinfunction "1_1") (pintype "passive"))
    )
    (net (code "11") (name "/Imeas_P1V8") (class "Default")
      (node (ref "C94") (pin "2") (pinfunction "2_2") (pintype "passive"))
      (node (ref "R168") (pin "1") (pinfunction "1_1") (pintype "passive"))
    )
    (net (code "12") (name "/Imeas_P2V5") (class "Default")
      (node (ref "C25") (pin "2") (pinfunction "2_2") (pintype "passive"))
      (node (ref "R26") (pin "1") (pinfunction "1_1") (pintype "passive"))
    )
    (net (code "13") (name "/Imeas_P2V5_VADJ") (class "Default")
      (node (ref "C24") (pin "2") (pinfunction "2_2") (pintype "passive"))
      (node (ref "R25") (pin "1") (pinfunction "1_1") (pintype "passive"))
    )
    (net (code "14") (name "/Imeas_P3V3") (class "Default")
      (node (ref "C26") (pin "2") (pinfunction "2_2") (pintype "passive"))
      (node (ref "R27") (pin "1") (pinfunction "1_1") (pintype "passive"))
    )
    (net (code "15") (name "/MIC_ADJ") (class "Default")
      (node (ref "C13") (pin "1") (pinfunction "1_1") (pintype "passive"))
      (node (ref "C14") (pin "1") (pinfunction "1_1") (pintype "passive"))
      (node (ref "IC12") (pin "1") (pinfunction "ADJ_1") (pintype "power_in"))
      (node (ref "IC6") (pin "1") (pinfunction "ADJ_1") (pintype "power_in"))
      (node (ref "R10") (pin "1") (pinfunction "1_1") (pintype "passive"))
      (node (ref "R11") (pin "1") (pinfunction "1_1") (pintype "passive"))
      (node (ref "R12") (pin "2") (pinfunction "2_2") (pintype "passive"))
      (node (ref "R13") (pin "2") (pinfunction "2_2") (pintype "passive"))
      (node (ref "R167") (pin "2") (pinfunction "2_2") (pintype "passive"))
      (node (ref "R7") (pin "1") (pinfunction "1_1") (pintype "passive"))
      (node (ref "R8") (pin "1") (pinfunction "1_1") (pintype "passive"))
    )
    (net (code "16") (name "/MIC_OUT") (class "Default")
      (node (ref "C12") (pin "2") (pinfunction "2_2") (pintype "passive"))
      (node (ref "C14") (pin "2") (pinfunction "2_2") (pintype "passive"))
      (node (ref "IC12") (pin "5") (pinfunction "OUT_5") (pintype "power_in"))
      (node (ref "R10") (pin "2") (pinfunction "2_2") (pintype "passive"))
      (node (ref "R11") (pin "2") (pinfunction "2_2") (pintype "passive"))
    )
    (net (code "17") (name "/MIC_SHUTDOWN") (class "Default")
      (node (ref "IC12") (pin "2") (pinfunction "SHUT_2") (pintype "power_in"))
      (node (ref "R9") (pin "2") (pinfunction "2_2") (pintype "passive"))
    )
    (net (code "19") (name "/TPS_EN") (class "Default")
      (node (ref "IC24") (pin "8") (pinfunction "VINA_8") (pintype "input"))
      (node (ref "R14") (pin "1") (pinfunction "1_1") (pintype "passive"))
    )
    (net (code "20") (name "/TPS_FB") (class "Default")
      (node (ref "C20") (pin "1") (pinfunction "1_1") (pintype "passive"))
      (node (ref "IC24") (pin "10") (pinfunction "FB_10") (pintype "input"))
      (node (ref "R16") (pin "1") (pinfunction "1_1") (pintype "passive"))
      (node (ref "R17") (pin "1") (pinfunction "1_1") (pintype "passive"))
      (node (ref "R19") (pin "2") (pinfunction "2_2") (pintype "passive"))
    )
    (net (code "21") (name "/TPS_LBI") (class "Default")
      (node (ref "IC24") (pin "7") (pinfunction "LBI_7") (pintype "input"))
      (node (ref "R18") (pin "2") (pinfunction "2_2") (pintype "passive"))
    )
    (net (code "22") (name "/TPS_LBO") (class "Default")
      (node (ref "IC24") (pin "6") (pinfunction "LBO_6") (pintype "input"))
    )
    (net (code "23") (name "/TPS_PG") (class "Default")
      (node (ref "IC24") (pin "13") (pinfunction "PG_13") (pintype "output"))
      (node (ref "R15") (pin "1") (pinfunction "1_1") (pintype "passive"))
    )
    (net (code "24") (name "/TPS_SW") (class "Default")
      (node (ref "IC24") (pin "14") (pinfunction "SW_14") (pintype "output"))
      (node (ref "IC24") (pin "15") (pinfunction "SW_15") (pintype "output"))
      (node (ref "L1") (pin "2") (pinfunction "2_2") (pintype "passive"))
    )
    (net (code "25") (name "/TPS_SYNC") (class "Default")
      (node (ref "IC24") (pin "5") (pinfunction "SYNC_5") (pintype "input"))
    )
    (net (code "26") (name "/TPS_VOUT") (class "Default")
      (node (ref "C15") (pin "2") (pinfunction "2_2") (pintype "passive"))
      (node (ref "C16") (pin "2") (pinfunction "2_2") (pintype "passive"))
      (node (ref "C17") (pin "2") (pinfunction "2_2") (pintype "passive"))
      (node (ref "C18") (pin "2") (pinfunction "2_2") (pintype "passive"))
      (node (ref "C20") (pin "2") (pinfunction "2_2") (pintype "passive"))
      (node (ref "L1") (pin "1") (pinfunction "1_1") (pintype "passive"))
      (node (ref "R15") (pin "2") (pinfunction "2_2") (pintype "passive"))
      (node (ref "R16") (pin "2") (pinfunction "2_2") (pintype "passive"))
      (node (ref "R17") (pin "2") (pinfunction "2_2") (pintype "passive"))
    )
    (net (code "27") (name "/VADJ") (class "Default")
      (node (ref "IC7") (pin "5") (pinfunction "RS-_5") (pintype "passive"))
      (node (ref "R21") (pin "2") (pinfunction "2_2") (pintype "passive"))
    )
    (net (code "28") (name "/VIN") (class "Default")
      (node (ref "C6") (pin "2") (pinfunction "2_2") (pintype "passive"))
      (node (ref "C7") (pin "2") (pinfunction "2_2") (pintype "passive"))
      (node (ref "IC4") (pin "7") (pinfunction "VIN_7") (pintype "input"))
    )
    (net (code "30") (name "/VOUT") (class "Default")
      (node (ref "C8") (pin "1") (pinfunction "1_1") (pintype "passive"))
      (node (ref "L2") (pin "1") (pinfunction "1_1") (pintype "passive"))
      (node (ref "R4") (pin "2") (pinfunction "2_2") (pintype "passive"))
    )
    (net (code "33") (name "GND") (class "Default")
      (node (ref "C10") (pin "1") (pinfunction "1_1") (pintype "passive"))
      (node (ref "C11") (pin "1") (pinfunction "1_1") (pintype "passive"))
      (node (ref "C12") (pin "1") (pinfunction "1_1") (pintype "passive"))
      (node (ref "C15") (pin "1") (pinfunction "1_1") (pintype "passive"))
      (node (ref "C16") (pin "1") (pinfunction "1_1") (pintype "passive"))
      (node (ref "C17") (pin "1") (pinfunction "1_1") (pintype "passive"))
      (node (ref "C18") (pin "1") (pinfunction "1_1") (pintype "passive"))
      (node (ref "C19") (pin "1") (pinfunction "1_1") (pintype "passive"))
      (node (ref "C21") (pin "1") (pinfunction "1_1") (pintype "passive"))
      (node (ref "C22") (pin "1") (pinfunction "1_1") (pintype "passive"))
      (node (ref "C24") (pin "1") (pinfunction "1_1") (pintype "passive"))
      (node (ref "C25") (pin "1") (pinfunction "1_1") (pintype "passive"))
      (node (ref "C254") (pin "1") (pinfunction "1_1") (pintype "passive"))
      (node (ref "C255") (pin "1") (pinfunction "1_1") (pintype "passive"))
      (node (ref "C256") (pin "1") (pinfunction "1_1") (pintype "passive"))
      (node (ref "C257") (pin "1") (pinfunction "1_1") (pintype "passive"))
      (node (ref "C258") (pin "1") (pinfunction "1_1") (pintype "passive"))
      (node (ref "C259") (pin "1") (pinfunction "1_1") (pintype "passive"))
      (node (ref "C26") (pin "1") (pinfunction "1_1") (pintype "passive"))
      (node (ref "C260") (pin "1") (pinfunction "1_1") (pintype "passive"))
      (node (ref "C261") (pin "1") (pinfunction "1_1") (pintype "passive"))
      (node (ref "C262") (pin "1") (pinfunction "1_1") (pintype "passive"))
      (node (ref "C263") (pin "1") (pinfunction "1_1") (pintype "passive"))
      (node (ref "C264") (pin "1") (pinfunction "1_1") (pintype "passive"))
      (node (ref "C265") (pin "1") (pinfunction "1_1") (pintype "passive"))
      (node (ref "C266") (pin "1") (pinfunction "1_1") (pintype "passive"))
      (node (ref "C267") (pin "1") (pinfunction "1_1") (pintype "passive"))
      (node (ref "C268") (pin "1") (pinfunction "1_1") (pintype "passive"))
      (node (ref "C269") (pin "1") (pinfunction "1_1") (pintype "passive"))
      (node (ref "C6") (pin "1") (pinfunction "1_1") (pintype "passive"))
      (node (ref "C7") (pin "1") (pinfunction "1_1") (pintype "passive"))
      (node (ref "C8") (pin "2") (pinfunction "2_2") (pintype "passive"))
      (node (ref "C9") (pin "1") (pinfunction "1_1") (pintype "passive"))
      (node (ref "C94") (pin "1") (pinfunction "1_1") (pintype "passive"))
      (node (ref "D2") (pin "2") (pinfunction "2_2") (pintype "passive"))
      (node (ref "IC12") (pin "3") (pinfunction "GND_3") (pintype "power_in"))
      (node (ref "IC23") (pin "1") (pinfunction "GND_1") (pintype "passive"))
      (node (ref "IC24") (pin "1") (pinfunction "PGND_1") (pintype "power_in"))
      (node (ref "IC24") (pin "11") (pinfunction "GND_11") (pintype "power_in"))
      (node (ref "IC24") (pin "12") (pinfunction "GND_12") (pintype "power_in"))
      (node (ref "IC24") (pin "16") (pinfunction "PGND_16") (pintype "power_in"))
      (node (ref "IC24") (pin "17") (pinfunction "PAD_17") (pintype "power_in"))
      (node (ref "IC24") (pin "9") (pinfunction "AGND_9") (pintype "power_in"))
      (node (ref "IC28") (pin "1") (pinfunction "GND_1") (pintype "passive"))
      (node (ref "IC4") (pin "6") (pinfunction "GND_6") (pintype "power_in"))
      (node (ref "IC5") (pin "1") (pinfunction "GND_1") (pintype "passive"))
      (node (ref "IC6") (pin "3") (pinfunction "GND_3") (pintype "power_in"))
      (node (ref "IC7") (pin "1") (pinfunction "GND_1") (pintype "passive"))
      (node (ref "IC8") (pin "1") (pinfunction "GND_1") (pintype "passive"))
      (node (ref "IC9") (pin "1") (pinfunction "GND_1") (pintype "passive"))
      (node (ref "R12") (pin "1") (pinfunction "1_1") (pintype "passive"))
      (node (ref "R13") (pin "1") (pinfunction "1_1") (pintype "passive"))
      (node (ref "R167") (pin "1") (pinfunction "1_1") (pintype "passive"))
      (node (ref "R18") (pin "1") (pinfunction "1_1") (pintype "passive"))
      (node (ref "R19") (pin "1") (pinfunction "1_1") (pintype "passive"))
      (node (ref "R5") (pin "1") (pinfunction "1_1") (pintype "passive"))
      (node (ref "R6") (pin "1") (pinfunction "1_1") (pintype "passive"))
      (node (ref "R9") (pin "1") (pinfunction "1_1") (pintype "passive"))
    )
    (net (code "34") (name "MIC_VIN") (class "Default")
      (node (ref "C10") (pin "2") (pinfunction "2_2") (pintype "passive"))
      (node (ref "IC12") (pin "4") (pinfunction "IN_4") (pintype "power_in"))
    )
    (net (code "35") (name "Net-(IC4-BOOT)") (class "Default")
      (node (ref "C5") (pin "1") (pinfunction "1_1") (pintype "passive"))
      (node (ref "IC4") (pin "1") (pinfunction "BOOT_1") (pintype "passive"))
    )
    (net (code "36") (name "Net-(IC4-PH)") (class "Default")
      (node (ref "C5") (pin "2") (pinfunction "2_2") (pintype "passive"))
      (node (ref "D2") (pin "1") (pinfunction "1_1") (pintype "passive"))
      (node (ref "IC4") (pin "8") (pinfunction "PH_8") (pintype "power_in"))
      (node (ref "L2") (pin "2") (pinfunction "2_2") (pintype "passive"))
    )
    (net (code "37") (name "Net-(IC4-VSENSE)") (class "Default")
      (node (ref "IC4") (pin "4") (pinfunction "VSENSE_4") (pintype "power_in"))
      (node (ref "R4") (pin "1") (pinfunction "1_1") (pintype "passive"))
      (node (ref "R5") (pin "2") (pinfunction "2_2") (pintype "passive"))
    )
    (net (code "38") (name "Net-(IC5-OUT)") (class "Default")
      (node (ref "IC5") (pin "2") (pinfunction "OUT_2") (pintype "passive"))
      (node (ref "R23") (pin "2") (pinfunction "2_2") (pintype "passive"))
    )
    (net (code "39") (name "Net-(IC6-SHUT)") (class "Default")
      (node (ref "IC6") (pin "2") (pinfunction "SHUT_2") (pintype "power_in"))
      (node (ref "R6") (pin "2") (pinfunction "2_2") (pintype "passive"))
    )
    (net (code "40") (name "Net-(IC7-OUT)") (class "Default")
      (node (ref "IC7") (pin "2") (pinfunction "OUT_2") (pintype "passive"))
      (node (ref "R25") (pin "2") (pinfunction "2_2") (pintype "passive"))
    )
    (net (code "41") (name "Net-(IC8-OUT)") (class "Default")
      (node (ref "IC8") (pin "2") (pinfunction "OUT_2") (pintype "passive"))
      (node (ref "R26") (pin "2") (pinfunction "2_2") (pintype "passive"))
    )
    (net (code "42") (name "Net-(IC9-OUT)") (class "Default")
      (node (ref "IC9") (pin "2") (pinfunction "OUT_2") (pintype "passive"))
      (node (ref "R27") (pin "2") (pinfunction "2_2") (pintype "passive"))
    )
    (net (code "43") (name "Net-(IC23-OUT)") (class "Default")
      (node (ref "IC23") (pin "2") (pinfunction "OUT_2") (pintype "passive"))
      (node (ref "R24") (pin "2") (pinfunction "2_2") (pintype "passive"))
    )
    (net (code "44") (name "Net-(IC28-OUT)") (class "Default")
      (node (ref "IC28") (pin "2") (pinfunction "OUT_2") (pintype "passive"))
      (node (ref "R168") (pin "2") (pinfunction "2_2") (pintype "passive"))
    )
    (net (code "45") (name "P1V0") (class "Default")
      (node (ref "C256") (pin "2") (pinfunction "2_2") (pintype "passive"))
      (node (ref "C257") (pin "2") (pinfunction "2_2") (pintype "passive"))
      (node (ref "C258") (pin "2") (pinfunction "2_2") (pintype "passive"))
      (node (ref "C259") (pin "2") (pinfunction "2_2") (pintype "passive"))
      (node (ref "IC5") (pin "4") (pinfunction "RS+_4") (pintype "passive"))
      (node (ref "R20") (pin "1") (pinfunction "1_1") (pintype "passive"))
      (node (ref "U1") (pin "A1") (pinfunction "VOUT_A1") (pintype "power_in"))
      (node (ref "U1") (pin "A2") (pinfunction "VOUT_A2") (pintype "power_in"))
      (node (ref "U1") (pin "A3") (pinfunction "VOUT_A3") (pintype "power_in"))
      (node (ref "U1") (pin "B1") (pinfunction "VOUT_B1") (pintype "power_in"))
      (node (ref "U1") (pin "B2") (pinfunction "VOUT_B2") (pintype "power_in"))
      (node (ref "U1") (pin "B3") (pinfunction "VOUT_B3") (pintype "power_in"))
      (node (ref "U1") (pin "C1") (pinfunction "VOUT_C1") (pintype "power_in"))
      (node (ref "U1") (pin "C2") (pinfunction "VOUT_C2") (pintype "power_in"))
      (node (ref "U1") (pin "C3") (pinfunction "VOUT_C3") (pintype "power_in"))
      (node (ref "U1") (pin "D1") (pinfunction "VOUT_D1") (pintype "power_in"))
      (node (ref "U1") (pin "D2") (pinfunction "VOUT_D2") (pintype "power_in"))
      (node (ref "U1") (pin "D3") (pinfunction "VOUT_D3") (pintype "power_in"))
    )
    (net (code "46") (name "P1V0_CORE") (class "Default")
      (node (ref "IC5") (pin "5") (pinfunction "RS-_5") (pintype "passive"))
      (node (ref "L3") (pin "1") (pinfunction "1_1") (pintype "passive"))
      (node (ref "R20") (pin "2") (pinfunction "2_2") (pintype "passive"))
    )
    (net (code "47") (name "P1V0_XCVR") (class "Default")
      (node (ref "L3") (pin "2") (pinfunction "2_2") (pintype "passive"))
    )
    (net (code "48") (name "P1V2") (class "Default")
      (node (ref "C262") (pin "2") (pinfunction "2_2") (pintype "passive"))
      (node (ref "C263") (pin "2") (pinfunction "2_2") (pintype "passive"))
      (node (ref "C264") (pin "2") (pinfunction "2_2") (pintype "passive"))
      (node (ref "C265") (pin "2") (pinfunction "2_2") (pintype "passive"))
      (node (ref "IC23") (pin "4") (pinfunction "RS+_4") (pintype "passive"))
      (node (ref "R22") (pin "1") (pinfunction "1_1") (pintype "passive"))
    )
    (net (code "49") (name "P1V2_DDR") (class "Default")
      (node (ref "IC23") (pin "5") (pinfunction "RS-_5") (pintype "passive"))
      (node (ref "R22") (pin "2") (pinfunction "2_2") (pintype "passive"))
    )
    (net (code "50") (name "P1V8") (class "Default")
      (node (ref "IC28") (pin "5") (pinfunction "RS-_5") (pintype "passive"))
      (node (ref "R164") (pin "2") (pinfunction "2_2") (pintype "passive"))
    )
    (net (code "51") (name "P1V8_LDO") (class "Default")
      (node (ref "C11") (pin "2") (pinfunction "2_2") (pintype "passive"))
      (node (ref "C13") (pin "2") (pinfunction "2_2") (pintype "passive"))
      (node (ref "IC28") (pin "4") (pinfunction "RS+_4") (pintype "passive"))
      (node (ref "IC6") (pin "5") (pinfunction "OUT_5") (pintype "power_in"))
      (node (ref "R164") (pin "1") (pinfunction "1_1") (pintype "passive"))
      (node (ref "R7") (pin "2") (pinfunction "2_2") (pintype "passive"))
      (node (ref "R8") (pin "2") (pinfunction "2_2") (pintype "passive"))
    )
    (net (code "52") (name "P2V5") (class "Default")
      (node (ref "C9") (pin "2") (pinfunction "2_2") (pintype "passive"))
      (node (ref "IC6") (pin "4") (pinfunction "IN_4") (pintype "power_in"))
      (node (ref "IC8") (pin "5") (pinfunction "RS-_5") (pintype "passive"))
      (node (ref "L4") (pin "1") (pinfunction "1_1") (pintype "passive"))
      (node (ref "L5") (pin "1") (pinfunction "1_1") (pintype "passive"))
      (node (ref "R165") (pin "2") (pinfunction "2_2") (pintype "passive"))
    )
    (net (code "53") (name "P2V5_Buck") (class "Default")
      (node (ref "IC7") (pin "4") (pinfunction "RS+_4") (pintype "passive"))
      (node (ref "IC8") (pin "4") (pinfunction "RS+_4") (pintype "passive"))
      (node (ref "R165") (pin "1") (pinfunction "1_1") (pintype "passive"))
      (node (ref "R21") (pin "1") (pinfunction "1_1") (pintype "passive"))
    )
    (net (code "54") (name "P2V5_PLL") (class "Default")
      (node (ref "L5") (pin "2") (pinfunction "2_2") (pintype "passive"))
    )
    (net (code "55") (name "P2V5_XCVR") (class "Default")
      (node (ref "L4") (pin "2") (pinfunction "2_2") (pintype "passive"))
    )
    (net (code "56") (name "P3V3") (class "Default")
      (node (ref "IC9") (pin "5") (pinfunction "RS-_5") (pintype "passive"))
      (node (ref "R166") (pin "2") (pinfunction "2_2") (pintype "passive"))
    )
    (net (code "57") (name "P3V3_M") (class "Default")
      (node (ref "C260") (pin "2") (pinfunction "2_2") (pintype "passive"))
      (node (ref "C261") (pin "2") (pinfunction "2_2") (pintype "passive"))
      (node (ref "C266") (pin "2") (pinfunction "2_2") (pintype "passive"))
      (node (ref "C267") (pin "2") (pinfunction "2_2") (pintype "passive"))
      (node (ref "C268") (pin "2") (pinfunction "2_2") (pintype "passive"))
      (node (ref "C269") (pin "2") (pinfunction "2_2") (pintype "passive"))
      (node (ref "IC23") (pin "3") (pinfunction "VCC_3") (pintype "passive"))
      (node (ref "IC28") (pin "3") (pinfunction "VCC_3") (pintype "passive"))
      (node (ref "IC5") (pin "3") (pinfunction "VCC_3") (pintype "passive"))
      (node (ref "IC7") (pin "3") (pinfunction "VCC_3") (pintype "passive"))
      (node (ref "IC8") (pin "3") (pinfunction "VCC_3") (pintype "passive"))
      (node (ref "IC9") (pin "3") (pinfunction "VCC_3") (pintype "passive"))
    )
    (net (code "58") (name "P3V3_buck") (class "Default")
      (node (ref "IC9") (pin "4") (pinfunction "RS+_4") (pintype "passive"))
      (node (ref "R166") (pin "1") (pinfunction "1_1") (pintype "passive"))
    )
    (net (code "59") (name "P5V0") (class "Default")
      (node (ref "C254") (pin "2") (pinfunction "2_2") (pintype "passive"))
      (node (ref "C255") (pin "2") (pinfunction "2_2") (pintype "passive"))
    )
    (net (code "60") (name "TPS_VIN") (class "Default")
      (node (ref "C19") (pin "2") (pinfunction "2_2") (pintype "passive"))
      (node (ref "C21") (pin "2") (pinfunction "2_2") (pintype "passive"))
      (node (ref "IC24") (pin "2") (pinfunction "VIN_2") (pintype "input"))
      (node (ref "IC24") (pin "3") (pinfunction "VIN_3") (pintype "input"))
      (node (ref "IC24") (pin "4") (pinfunction "EN_4") (pintype "input"))
      (node (ref "R14") (pin "2") (pinfunction "2_2") (pintype "passive"))
    )
    (net (code "61") (name "unconnected-(C23-Pad1)") (class "Default")
      (node (ref "C23") (pin "1") (pinfunction "1_1") (pintype "passive"))
    )
    (net (code "62") (name "unconnected-(IC4-NC-Pad2)") (class "Default")
      (node (ref "IC4") (pin "2") (pinfunction "NC_2") (pintype "passive"))
    )
    (net (code "63") (name "unconnected-(IC4-NC-Pad3)") (class "Default")
      (node (ref "IC4") (pin "3") (pinfunction "NC_3") (pintype "passive"))
    )
    (net (code "64") (name "unconnected-(IC21-BOOT-Pad13)") (class "Default")
      (node (ref "IC21") (pin "13") (pinfunction "BOOT_13") (pintype "input"))
    )
    (net (code "65") (name "unconnected-(IC21-COMP-Pad8)") (class "Default")
      (node (ref "IC21") (pin "8") (pinfunction "COMP_8") (pintype "output"))
    )
    (net (code "66") (name "unconnected-(IC21-EN-Pad10)") (class "Default")
      (node (ref "IC21") (pin "10") (pinfunction "EN_10") (pintype "input"))
    )
    (net (code "67") (name "unconnected-(IC21-GND-Pad2)") (class "Default")
      (node (ref "IC21") (pin "2") (pinfunction "GND_2") (pintype "power_in"))
    )
    (net (code "68") (name "unconnected-(IC21-GND-Pad3)") (class "Default")
      (node (ref "IC21") (pin "3") (pinfunction "GND_3") (pintype "power_in"))
    )
    (net (code "69") (name "unconnected-(IC21-PH-Pad11)") (class "Default")
      (node (ref "IC21") (pin "11") (pinfunction "PH_11") (pintype "bidirectional"))
    )
    (net (code "70") (name "unconnected-(IC21-PH-Pad12)") (class "Default")
      (node (ref "IC21") (pin "12") (pinfunction "PH_12") (pintype "bidirectional"))
    )
    (net (code "71") (name "unconnected-(IC21-PVIN-Pad4)") (class "Default")
      (node (ref "IC21") (pin "4") (pinfunction "PVIN_4") (pintype "input"))
    )
    (net (code "72") (name "unconnected-(IC21-PVIN-Pad5)") (class "Default")
      (node (ref "IC21") (pin "5") (pinfunction "PVIN_5") (pintype "input"))
    )
    (net (code "73") (name "unconnected-(IC21-PWPAD-Pad15)") (class "Default")
      (node (ref "IC21") (pin "15") (pinfunction "PWPAD_15") (pintype "power_in"))
    )
    (net (code "74") (name "unconnected-(IC21-PWRGD-Pad14)") (class "Default")
      (node (ref "IC21") (pin "14") (pinfunction "PWRGD_14") (pintype "output"))
    )
    (net (code "75") (name "unconnected-(IC21-RT{slash}CLK-Pad1)") (class "Default")
      (node (ref "IC21") (pin "1") (pinfunction "RT/CLK_1") (pintype "input"))
    )
    (net (code "76") (name "unconnected-(IC21-SS{slash}TR-Pad9)") (class "Default")
      (node (ref "IC21") (pin "9") (pinfunction "SS/TR_9") (pintype "input"))
    )
    (net (code "77") (name "unconnected-(IC21-VIN-Pad6)") (class "Default")
      (node (ref "IC21") (pin "6") (pinfunction "VIN_6") (pintype "input"))
    )
    (net (code "78") (name "unconnected-(IC21-VSENSE-Pad7)") (class "Default")
      (node (ref "IC21") (pin "7") (pinfunction "VSENSE_7") (pintype "input"))
    )
    (net (code "79") (name "unconnected-(U1A-ADJ-PadA7)") (class "Default")
      (node (ref "U1") (pin "A7") (pinfunction "ADJ_A7") (pintype "input"))
    )
    (net (code "80") (name "unconnected-(U1A-AUX-PadG3)") (class "Default")
      (node (ref "U1") (pin "G3") (pinfunction "AUX_G3") (pintype "power_in"))
    )
    (net (code "81") (name "unconnected-(U1A-BIAS-PadG4)") (class "Default")
      (node (ref "U1") (pin "G4") (pinfunction "BIAS_G4") (pintype "power_in"))
    )
    (net (code "82") (name "unconnected-(U1A-FIN-PadJ8)") (class "Default")
      (node (ref "U1") (pin "J8") (pinfunction "FIN_J8") (pintype "input"))
    )
    (net (code "83") (name "unconnected-(U1A-FIN-PadK8)") (class "Default")
      (node (ref "U1") (pin "K8") (pinfunction "FIN_K8") (pintype "input"))
    )
    (net (code "84") (name "unconnected-(U1A-FIN-PadL8)") (class "Default")
      (node (ref "U1") (pin "L8") (pinfunction "FIN_L8") (pintype "input"))
    )
    (net (code "85") (name "unconnected-(U1A-PGOOD-PadB7)") (class "Default")
      (node (ref "U1") (pin "B7") (pinfunction "PGOOD_B7") (pintype "open_collector"))
    )
    (net (code "86") (name "unconnected-(U1A-RT-PadB6)") (class "Default")
      (node (ref "U1") (pin "B6") (pinfunction "RT_B6") (pintype "input"))
    )
    (net (code "87") (name "unconnected-(U1A-RUN{slash}SS-PadG8)") (class "Default")
      (node (ref "U1") (pin "G8") (pinfunction "RUN/SS_G8") (pintype "input"))
    )
    (net (code "88") (name "unconnected-(U1A-SHARE-PadA6)") (class "Default")
      (node (ref "U1") (pin "A6") (pinfunction "SHARE_A6") (pintype "passive"))
    )
    (net (code "89") (name "unconnected-(U1A-SYNC-PadB8)") (class "Default")
      (node (ref "U1") (pin "B8") (pinfunction "SYNC_B8") (pintype "input"))
    )
    (net (code "90") (name "unconnected-(U1A-VIN-PadJ1)") (class "Default")
      (node (ref "U1") (pin "J1") (pinfunction "VIN_J1") (pintype "power_in"))
    )
    (net (code "91") (name "unconnected-(U1A-VIN-PadJ2)") (class "Default")
      (node (ref "U1") (pin "J2") (pinfunction "VIN_J2") (pintype "power_in"))
    )
    (net (code "92") (name "unconnected-(U1A-VIN-PadJ3)") (class "Default")
      (node (ref "U1") (pin "J3") (pinfunction "VIN_J3") (pintype "power_in"))
    )
    (net (code "93") (name "unconnected-(U1A-VIN-PadK1)") (class "Default")
      (node (ref "U1") (pin "K1") (pinfunction "VIN_K1") (pintype "power_in"))
    )
    (net (code "94") (name "unconnected-(U1A-VIN-PadK2)") (class "Default")
      (node (ref "U1") (pin "K2") (pinfunction "VIN_K2") (pintype "power_in"))
    )
    (net (code "95") (name "unconnected-(U1A-VIN-PadK3)") (class "Default")
      (node (ref "U1") (pin "K3") (pinfunction "VIN_K3") (pintype "power_in"))
    )
    (net (code "96") (name "unconnected-(U1A-VIN-PadL1)") (class "Default")
      (node (ref "U1") (pin "L1") (pinfunction "VIN_L1") (pintype "power_in"))
    )
    (net (code "97") (name "unconnected-(U1A-VIN-PadL2)") (class "Default")
      (node (ref "U1") (pin "L2") (pinfunction "VIN_L2") (pintype "power_in"))
    )
    (net (code "98") (name "unconnected-(U1A-VIN-PadL3)") (class "Default")
      (node (ref "U1") (pin "L3") (pinfunction "VIN_L3") (pintype "power_in"))
    )
    (net (code "99") (name "unconnected-(U3A-ADJ-PadA7)") (class "Default")
      (node (ref "U3") (pin "A7") (pinfunction "ADJ_A7") (pintype "input"))
    )
    (net (code "100") (name "unconnected-(U3A-AUX-PadG3)") (class "Default")
      (node (ref "U3") (pin "G3") (pinfunction "AUX_G3") (pintype "power_in"))
    )
    (net (code "101") (name "unconnected-(U3A-BIAS-PadG4)") (class "Default")
      (node (ref "U3") (pin "G4") (pinfunction "BIAS_G4") (pintype "power_in"))
    )
    (net (code "102") (name "unconnected-(U3A-FIN-PadJ8)") (class "Default")
      (node (ref "U3") (pin "J8") (pinfunction "FIN_J8") (pintype "input"))
    )
    (net (code "103") (name "unconnected-(U3A-FIN-PadK8)") (class "Default")
      (node (ref "U3") (pin "K8") (pinfunction "FIN_K8") (pintype "input"))
    )
    (net (code "104") (name "unconnected-(U3A-FIN-PadL8)") (class "Default")
      (node (ref "U3") (pin "L8") (pinfunction "FIN_L8") (pintype "input"))
    )
    (net (code "105") (name "unconnected-(U3A-PGOOD-PadB7)") (class "Default")
      (node (ref "U3") (pin "B7") (pinfunction "PGOOD_B7") (pintype "open_collector"))
    )
    (net (code "106") (name "unconnected-(U3A-RT-PadB6)") (class "Default")
      (node (ref "U3") (pin "B6") (pinfunction "RT_B6") (pintype "input"))
    )
    (net (code "107") (name "unconnected-(U3A-RUN{slash}SS-PadG8)") (class "Default")
      (node (ref "U3") (pin "G8") (pinfunction "RUN/SS_G8") (pintype "input"))
    )
    (net (code "108") (name "unconnected-(U3A-SHARE-PadA6)") (class "Default")
      (node (ref "U3") (pin "A6") (pinfunction "SHARE_A6") (pintype "passive"))
    )
    (net (code "109") (name "unconnected-(U3A-SYNC-PadB8)") (class "Default")
      (node (ref "U3") (pin "B8") (pinfunction "SYNC_B8") (pintype "input"))
    )
    (net (code "110") (name "unconnected-(U3A-VIN-PadJ1)") (class "Default")
      (node (ref "U3") (pin "J1") (pinfunction "VIN_J1") (pintype "power_in"))
    )
    (net (code "111") (name "unconnected-(U3A-VIN-PadJ2)") (class "Default")
      (node (ref "U3") (pin "J2") (pinfunction "VIN_J2") (pintype "power_in"))
    )
    (net (code "112") (name "unconnected-(U3A-VIN-PadJ3)") (class "Default")
      (node (ref "U3") (pin "J3") (pinfunction "VIN_J3") (pintype "power_in"))
    )
    (net (code "113") (name "unconnected-(U3A-VIN-PadK1)") (class "Default")
      (node (ref "U3") (pin "K1") (pinfunction "VIN_K1") (pintype "power_in"))
    )
    (net (code "114") (name "unconnected-(U3A-VIN-PadK2)") (class "Default")
      (node (ref "U3") (pin "K2") (pinfunction "VIN_K2") (pintype "power_in"))
    )
    (net (code "115") (name "unconnected-(U3A-VIN-PadK3)") (class "Default")
      (node (ref "U3") (pin "K3") (pinfunction "VIN_K3") (pintype "power_in"))
    )
    (net (code "116") (name "unconnected-(U3A-VIN-PadL1)") (class "Default")
      (node (ref "U3") (pin "L1") (pinfunction "VIN_L1") (pintype "power_in"))
    )
    (net (code "117") (name "unconnected-(U3A-VIN-PadL2)") (class "Default")
      (node (ref "U3") (pin "L2") (pinfunction "VIN_L2") (pintype "power_in"))
    )
    (net (code "118") (name "unconnected-(U3A-VIN-PadL3)") (class "Default")
      (node (ref "U3") (pin "L3") (pinfunction "VIN_L3") (pintype "power_in"))
    )
    (net (code "119") (name "unconnected-(U3A-VOUT-PadA1)") (class "Default")
      (node (ref "U3") (pin "A1") (pinfunction "VOUT_A1") (pintype "power_in"))
    )
    (net (code "120") (name "unconnected-(U3A-VOUT-PadA2)") (class "Default")
      (node (ref "U3") (pin "A2") (pinfunction "VOUT_A2") (pintype "power_in"))
    )
    (net (code "121") (name "unconnected-(U3A-VOUT-PadA3)") (class "Default")
      (node (ref "U3") (pin "A3") (pinfunction "VOUT_A3") (pintype "power_in"))
    )
    (net (code "122") (name "unconnected-(U3A-VOUT-PadB1)") (class "Default")
      (node (ref "U3") (pin "B1") (pinfunction "VOUT_B1") (pintype "power_in"))
    )
    (net (code "123") (name "unconnected-(U3A-VOUT-PadB2)") (class "Default")
      (node (ref "U3") (pin "B2") (pinfunction "VOUT_B2") (pintype "power_in"))
    )
    (net (code "124") (name "unconnected-(U3A-VOUT-PadB3)") (class "Default")
      (node (ref "U3") (pin "B3") (pinfunction "VOUT_B3") (pintype "power_in"))
    )
    (net (code "125") (name "unconnected-(U3A-VOUT-PadC1)") (class "Default")
      (node (ref "U3") (pin "C1") (pinfunction "VOUT_C1") (pintype "power_in"))
    )
    (net (code "126") (name "unconnected-(U3A-VOUT-PadC2)") (class "Default")
      (node (ref "U3") (pin "C2") (pinfunction "VOUT_C2") (pintype "power_in"))
    )
    (net (code "127") (name "unconnected-(U3A-VOUT-PadC3)") (class "Default")
      (node (ref "U3") (pin "C3") (pinfunction "VOUT_C3") (pintype "power_in"))
    )
    (net (code "128") (name "unconnected-(U3A-VOUT-PadD1)") (class "Default")
      (node (ref "U3") (pin "D1") (pinfunction "VOUT_D1") (pintype "power_in"))
    )
    (net (code "129") (name "unconnected-(U3A-VOUT-PadD2)") (class "Default")
      (node (ref "U3") (pin "D2") (pinfunction "VOUT_D2") (pintype "power_in"))
    )
    (net (code "130") (name "unconnected-(U3A-VOUT-PadD3)") (class "Default")
      (node (ref "U3") (pin "D3") (pinfunction "VOUT_D3") (pintype "power_in"))
    )
    (net (code "131") (name "unconnected-(U6A-ADJ-PadA7)") (class "Default")
      (node (ref "U6") (pin "A7") (pinfunction "ADJ_A7") (pintype "input"))
    )
    (net (code "132") (name "unconnected-(U6A-AUX-PadG3)") (class "Default")
      (node (ref "U6") (pin "G3") (pinfunction "AUX_G3") (pintype "power_in"))
    )
    (net (code "133") (name "unconnected-(U6A-BIAS-PadG4)") (class "Default")
      (node (ref "U6") (pin "G4") (pinfunction "BIAS_G4") (pintype "power_in"))
    )
    (net (code "134") (name "unconnected-(U6A-FIN-PadJ8)") (class "Default")
      (node (ref "U6") (pin "J8") (pinfunction "FIN_J8") (pintype "input"))
    )
    (net (code "135") (name "unconnected-(U6A-FIN-PadK8)") (class "Default")
      (node (ref "U6") (pin "K8") (pinfunction "FIN_K8") (pintype "input"))
    )
    (net (code "136") (name "unconnected-(U6A-FIN-PadL8)") (class "Default")
      (node (ref "U6") (pin "L8") (pinfunction "FIN_L8") (pintype "input"))
    )
    (net (code "137") (name "unconnected-(U6A-PGOOD-PadB7)") (class "Default")
      (node (ref "U6") (pin "B7") (pinfunction "PGOOD_B7") (pintype "open_collector"))
    )
    (net (code "138") (name "unconnected-(U6A-RT-PadB6)") (class "Default")
      (node (ref "U6") (pin "B6") (pinfunction "RT_B6") (pintype "input"))
    )
    (net (code "139") (name "unconnected-(U6A-RUN{slash}SS-PadG8)") (class "Default")
      (node (ref "U6") (pin "G8") (pinfunction "RUN/SS_G8") (pintype "input"))
    )
    (net (code "140") (name "unconnected-(U6A-SHARE-PadA6)") (class "Default")
      (node (ref "U6") (pin "A6") (pinfunction "SHARE_A6") (pintype "passive"))
    )
    (net (code "141") (name "unconnected-(U6A-SYNC-PadB8)") (class "Default")
      (node (ref "U6") (pin "B8") (pinfunction "SYNC_B8") (pintype "input"))
    )
    (net (code "142") (name "unconnected-(U6A-VIN-PadJ1)") (class "Default")
      (node (ref "U6") (pin "J1") (pinfunction "VIN_J1") (pintype "power_in"))
    )
    (net (code "143") (name "unconnected-(U6A-VIN-PadJ2)") (class "Default")
      (node (ref "U6") (pin "J2") (pinfunction "VIN_J2") (pintype "power_in"))
    )
    (net (code "144") (name "unconnected-(U6A-VIN-PadJ3)") (class "Default")
      (node (ref "U6") (pin "J3") (pinfunction "VIN_J3") (pintype "power_in"))
    )
    (net (code "145") (name "unconnected-(U6A-VIN-PadK1)") (class "Default")
      (node (ref "U6") (pin "K1") (pinfunction "VIN_K1") (pintype "power_in"))
    )
    (net (code "146") (name "unconnected-(U6A-VIN-PadK2)") (class "Default")
      (node (ref "U6") (pin "K2") (pinfunction "VIN_K2") (pintype "power_in"))
    )
    (net (code "147") (name "unconnected-(U6A-VIN-PadK3)") (class "Default")
      (node (ref "U6") (pin "K3") (pinfunction "VIN_K3") (pintype "power_in"))
    )
    (net (code "148") (name "unconnected-(U6A-VIN-PadL1)") (class "Default")
      (node (ref "U6") (pin "L1") (pinfunction "VIN_L1") (pintype "power_in"))
    )
    (net (code "149") (name "unconnected-(U6A-VIN-PadL2)") (class "Default")
      (node (ref "U6") (pin "L2") (pinfunction "VIN_L2") (pintype "power_in"))
    )
    (net (code "150") (name "unconnected-(U6A-VIN-PadL3)") (class "Default")
      (node (ref "U6") (pin "L3") (pinfunction "VIN_L3") (pintype "power_in"))
    )
    (net (code "151") (name "unconnected-(U6A-VOUT-PadA1)") (class "Default")
      (node (ref "U6") (pin "A1") (pinfunction "VOUT_A1") (pintype "power_in"))
    )
    (net (code "152") (name "unconnected-(U6A-VOUT-PadA2)") (class "Default")
      (node (ref "U6") (pin "A2") (pinfunction "VOUT_A2") (pintype "power_in"))
    )
    (net (code "153") (name "unconnected-(U6A-VOUT-PadA3)") (class "Default")
      (node (ref "U6") (pin "A3") (pinfunction "VOUT_A3") (pintype "power_in"))
    )
    (net (code "154") (name "unconnected-(U6A-VOUT-PadB1)") (class "Default")
      (node (ref "U6") (pin "B1") (pinfunction "VOUT_B1") (pintype "power_in"))
    )
    (net (code "155") (name "unconnected-(U6A-VOUT-PadB2)") (class "Default")
      (node (ref "U6") (pin "B2") (pinfunction "VOUT_B2") (pintype "power_in"))
    )
    (net (code "156") (name "unconnected-(U6A-VOUT-PadB3)") (class "Default")
      (node (ref "U6") (pin "B3") (pinfunction "VOUT_B3") (pintype "power_in"))
    )
    (net (code "157") (name "unconnected-(U6A-VOUT-PadC1)") (class "Default")
      (node (ref "U6") (pin "C1") (pinfunction "VOUT_C1") (pintype "power_in"))
    )
    (net (code "158") (name "unconnected-(U6A-VOUT-PadC2)") (class "Default")
      (node (ref "U6") (pin "C2") (pinfunction "VOUT_C2") (pintype "power_in"))
    )
    (net (code "159") (name "unconnected-(U6A-VOUT-PadC3)") (class "Default")
      (node (ref "U6") (pin "C3") (pinfunction "VOUT_C3") (pintype "power_in"))
    )
    (net (code "160") (name "unconnected-(U6A-VOUT-PadD1)") (class "Default")
      (node (ref "U6") (pin "D1") (pinfunction "VOUT_D1") (pintype "power_in"))
    )
    (net (code "161") (name "unconnected-(U6A-VOUT-PadD2)") (class "Default")
      (node (ref "U6") (pin "D2") (pinfunction "VOUT_D2") (pintype "power_in"))
    )
    (net (code "162") (name "unconnected-(U6A-VOUT-PadD3)") (class "Default")
      (node (ref "U6") (pin "D3") (pinfunction "VOUT_D3") (pintype "power_in"))
    )
  )
)
